# flame_sensor.net
KiCad netlist of a schematic drawn in EAGLE
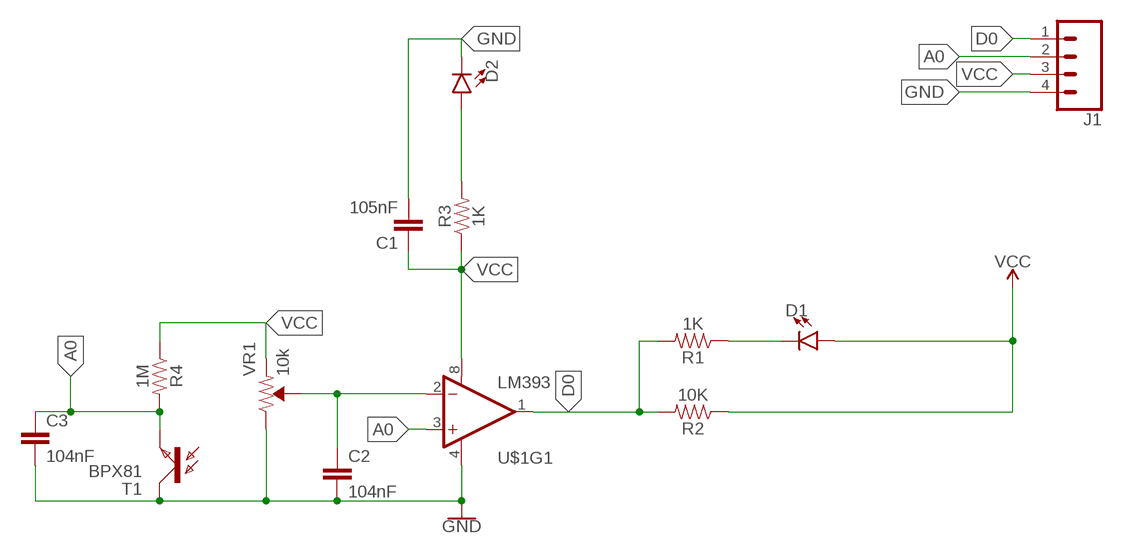
[diagram p0: schematic, sheet 1]

(export (version "E")
  (design (tool "Eeschema 10.0.6"))
  (components
    (comp (ref "C1")
      (value "105nF")
      (footprint "eagle-import:1206")
      (libsource (lib "eagle-import") (part "2.2UF-1206-50V-10%"))
    )
    (comp (ref "C2")
      (value "104nF")
      (footprint "eagle-import:1206")
      (libsource (lib "eagle-import") (part "2.2UF-1206-50V-10%"))
    )
    (comp (ref "C3")
      (value "104nF")
      (footprint "eagle-import:1206")
      (libsource (lib "eagle-import") (part "2.2UF-1206-50V-10%"))
    )
    (comp (ref "D1")
      (value "LED1206")
      (footprint "eagle-import:LED-1206")
      (libsource (lib "eagle-import") (part "LED1206"))
    )
    (comp (ref "D2")
      (value "LED1206")
      (footprint "eagle-import:LED-1206")
      (libsource (lib "eagle-import") (part "LED1206"))
    )
    (comp (ref "J1")
      (value "CONN_04")
      (footprint "eagle-import:1X04")
      (libsource (lib "eagle-import") (part "CONN_04"))
    )
    (comp (ref "R1")
      (value "1K")
      (footprint "eagle-import:0603")
      (libsource (lib "eagle-import") (part "0.05OHM-0603-1/5W-1%"))
    )
    (comp (ref "R2")
      (value "10K")
      (footprint "eagle-import:0603")
      (libsource (lib "eagle-import") (part "0.05OHM-0603-1/5W-1%"))
    )
    (comp (ref "R3")
      (value "1K")
      (footprint "eagle-import:0603")
      (libsource (lib "eagle-import") (part "0.05OHM-0603-1/5W-1%"))
    )
    (comp (ref "R4")
      (value "1M")
      (footprint "eagle-import:0603")
      (libsource (lib "eagle-import") (part "0.05OHM-0603-1/5W-1%"))
    )
    (comp (ref "T1")
      (value "BPX81")
      (footprint "eagle-import:BPX81")
      (libsource (lib "eagle-import") (part "BPX81"))
    )
    (comp (ref "U$1")
      (value "LM393")
      (footprint "eagle-import:SO08")
      (libsource (lib "eagle-import") (part "LM393"))
    )
    (comp (ref "VR1")
      (value "10k")
      (footprint "eagle-import:TRIMPOT-SMD-5MM")
      (libsource (lib "eagle-import") (part "TRIMPOT-SMD-5MM-CLOSED-1/4W-20%"))
    )
  )
  (nets
    (net (code "1") (name "A0") (class "Default")
      (node (ref "C3") (pin "1") (pinfunction "1_1") (pintype "passive"))
      (node (ref "J1") (pin "2") (pinfunction "2_2") (pintype "passive"))
      (node (ref "R4") (pin "2") (pinfunction "2_2") (pintype "passive"))
      (node (ref "T1") (pin "E") (pinfunction "E_E") (pintype "passive"))
      (node (ref "U$1") (pin "3") (pinfunction "+IN_3") (pintype "input"))
    )
    (net (code "2") (name "D0") (class "Default")
      (node (ref "J1") (pin "1") (pinfunction "1_1") (pintype "passive"))
      (node (ref "R1") (pin "2") (pinfunction "2_2") (pintype "passive"))
      (node (ref "R2") (pin "2") (pinfunction "2_2") (pintype "passive"))
      (node (ref "U$1") (pin "1") (pinfunction "OUT_1") (pintype "output"))
    )
    (net (code "3") (name "GND") (class "Default")
      (node (ref "C1") (pin "2") (pinfunction "2_2") (pintype "passive"))
      (node (ref "C2") (pin "2") (pinfunction "2_2") (pintype "passive"))
      (node (ref "C3") (pin "2") (pinfunction "2_2") (pintype "passive"))
      (node (ref "D2") (pin "C") (pinfunction "C_C") (pintype "passive"))
      (node (ref "J1") (pin "4") (pinfunction "4_4") (pintype "passive"))
      (node (ref "T1") (pin "C") (pinfunction "C_C") (pintype "passive"))
      (node (ref "U$1") (pin "4") (pinfunction "V-_4") (pintype "power_in"))
      (node (ref "VR1") (pin "C") (pinfunction "CW_C") (pintype "passive"))
    )
    (net (code "4") (name "Net-(D1-PadC)") (class "Default")
      (node (ref "D1") (pin "C") (pinfunction "C_C") (pintype "passive"))
      (node (ref "R1") (pin "1") (pinfunction "1_1") (pintype "passive"))
    )
    (net (code "5") (name "Net-(D2-PadA)") (class "Default")
      (node (ref "D2") (pin "A") (pinfunction "A_A") (pintype "passive"))
      (node (ref "R3") (pin "2") (pinfunction "2_2") (pintype "passive"))
    )
    (net (code "6") (name "Net-(U$1A--IN)") (class "Default")
      (node (ref "C2") (pin "1") (pinfunction "1_1") (pintype "passive"))
      (node (ref "U$1") (pin "2") (pinfunction "-IN_2") (pintype "input"))
      (node (ref "VR1") (pin "B") (pinfunction "WIPER_B") (pintype "passive"))
    )
    (net (code "7") (name "VCC") (class "Default")
      (node (ref "C1") (pin "1") (pinfunction "1_1") (pintype "passive"))
      (node (ref "D1") (pin "A") (pinfunction "A_A") (pintype "passive"))
      (node (ref "J1") (pin "3") (pinfunction "3_3") (pintype "passive"))
      (node (ref "R2") (pin "1") (pinfunction "1_1") (pintype "passive"))
      (node (ref "R3") (pin "1") (pinfunction "1_1") (pintype "passive"))
      (node (ref "R4") (pin "1") (pinfunction "1_1") (pintype "passive"))
      (node (ref "U$1") (pin "8") (pinfunction "V+_8") (pintype "power_in"))
      (node (ref "VR1") (pin "A") (pinfunction "CCW_A") (pintype "passive"))
    )
  )
)
